# Main.net
KiCad netlist of a schematic drawn in Altium Designer
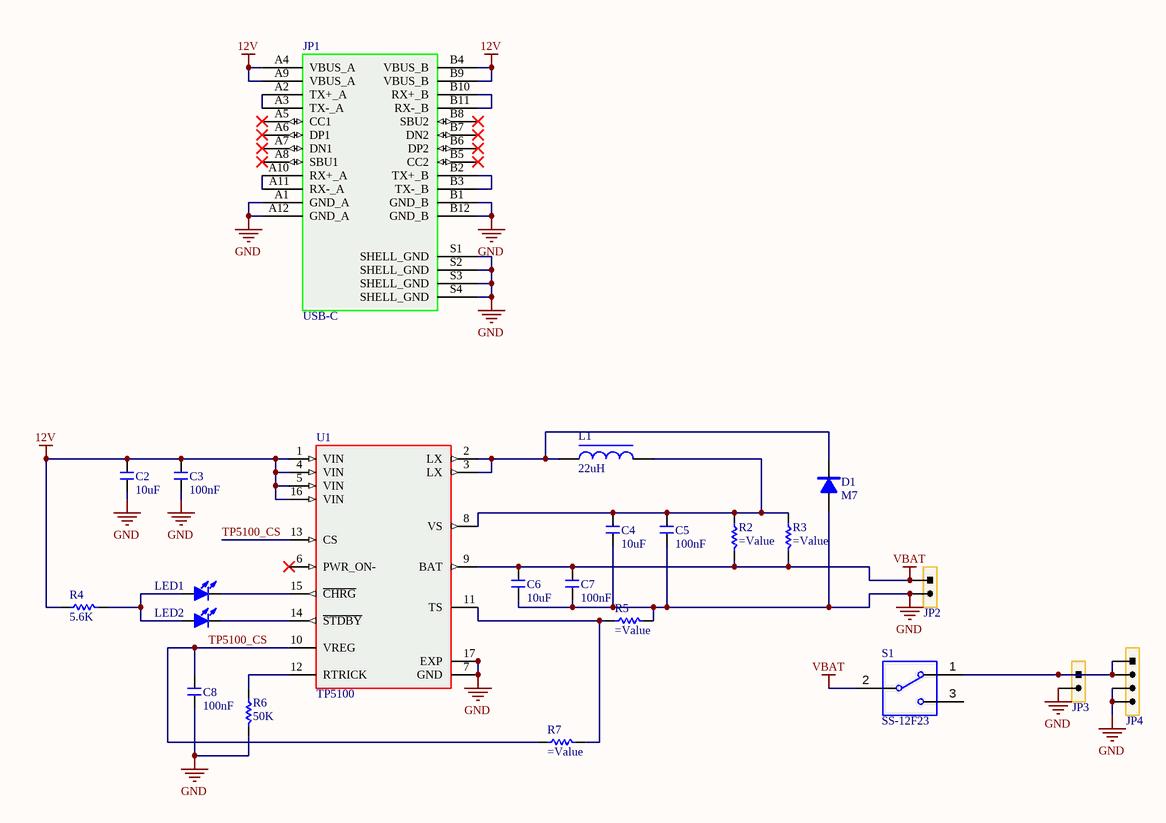
[diagram p0: Main.SchDoc]

(export (version "E")
  (design (tool "Eeschema 10.0.6"))
  (components
    (comp (ref "C2")
      (value "10uF")
      (footprint "C 0805")
      (description "Non-polar patch capacitor")
      (fields (field (name "版权归属") "源创客"))
      (libsource (lib "Passive (Resistor-Capacitor-Inductor-Veristor-Ferrite)") (part "C"))
    )
    (comp (ref "C3")
      (value "100nF")
      (footprint "C 0805")
      (description "Non-polar patch capacitor")
      (fields (field (name "版权归属") "源创客"))
      (libsource (lib "Passive (Resistor-Capacitor-Inductor-Veristor-Ferrite)") (part "C"))
    )
    (comp (ref "C4")
      (value "10uF")
      (footprint "C 0805")
      (description "Non-polar patch capacitor")
      (fields (field (name "版权归属") "源创客"))
      (libsource (lib "Passive (Resistor-Capacitor-Inductor-Veristor-Ferrite)") (part "C"))
    )
    (comp (ref "C5")
      (value "100nF")
      (footprint "C 0805")
      (description "Non-polar patch capacitor")
      (fields (field (name "版权归属") "源创客"))
      (libsource (lib "Passive (Resistor-Capacitor-Inductor-Veristor-Ferrite)") (part "C"))
    )
    (comp (ref "C6")
      (value "10uF")
      (footprint "C 0805")
      (description "Non-polar patch capacitor")
      (fields (field (name "版权归属") "源创客"))
      (libsource (lib "Passive (Resistor-Capacitor-Inductor-Veristor-Ferrite)") (part "C"))
    )
    (comp (ref "C7")
      (value "100nF")
      (footprint "C 0805")
      (description "Non-polar patch capacitor")
      (fields (field (name "版权归属") "源创客"))
      (libsource (lib "Passive (Resistor-Capacitor-Inductor-Veristor-Ferrite)") (part "C"))
    )
    (comp (ref "C8")
      (value "100nF")
      (footprint "C 0805")
      (description "Non-polar patch capacitor")
      (fields (field (name "版权归属") "源创客"))
      (libsource (lib "Passive (Resistor-Capacitor-Inductor-Veristor-Ferrite)") (part "C"))
    )
    (comp (ref "D1")
      (value "M7")
      (footprint "SMA")
      (description "Rectifier diode")
      (fields (field (name "版权归属") "源创客"))
      (libsource (lib "Diode-Zener-Rectifier Bridge") (part "M7"))
    )
    (comp (ref "JP1")
      (value "USB-C")
      (footprint "USB-C-RIGHT")
      (libsource (lib "IO (Power-USB-Serial-VGA-RJ-Audio-Buzzer)") (part "USB-C-RIGHT"))
    )
    (comp (ref "JP2")
      (value "HDR-1X2")
      (footprint "XH2.54-2P_H")
      (description "2P Connector")
      (fields (field (name "版权归属") "源创客"))
      (libsource (lib "Connectors") (part "Header 2"))
    )
    (comp (ref "JP3")
      (value "HDR-1X2")
      (footprint "XH2.54-2P_H")
      (description "2P Connector")
      (fields (field (name "版权归属") "源创客"))
      (libsource (lib "Connectors") (part "Header 2"))
    )
    (comp (ref "JP4")
      (value "HDR-1X4")
      (footprint "HDR-1X4")
      (description "4P Connector")
      (fields (field (name "版权归属") "源创客"))
      (libsource (lib "Connectors") (part "Header 4"))
    )
    (comp (ref "L1")
      (value "22uH")
      (footprint "CD54")
      (description "Chip power inductor")
      (fields (field (name "版权归属") "源创客"))
      (libsource (lib "Passive (Resistor-Capacitor-Inductor-Veristor-Ferrite)") (part "L-CD"))
    )
    (comp (ref "LED1")
      (value "LED-SMD")
      (footprint "LED 0603R")
      (description "Patch LED")
      (fields (field (name "版权归属") "源创客"))
      (libsource (lib "LED") (part "LED-SMD"))
    )
    (comp (ref "LED2")
      (value "LED-SMD")
      (footprint "LED 0603B")
      (description "Patch LED")
      (fields (field (name "版权归属") "源创客"))
      (libsource (lib "LED") (part "LED-SMD"))
    )
    (comp (ref "R2")
      (value "~")
      (footprint "R 1206")
      (description "Chip resistor")
      (fields (field (name "版权归属") "源创客"))
      (libsource (lib "Passive (Resistor-Capacitor-Inductor-Veristor-Ferrite)") (part "R"))
    )
    (comp (ref "R3")
      (value "~")
      (footprint "R 1206")
      (description "Chip resistor")
      (fields (field (name "版权归属") "源创客"))
      (libsource (lib "Passive (Resistor-Capacitor-Inductor-Veristor-Ferrite)") (part "R"))
    )
    (comp (ref "R4")
      (value "5.6K")
      (footprint "R 0805")
      (description "Chip resistor")
      (fields (field (name "版权归属") "源创客"))
      (libsource (lib "Passive (Resistor-Capacitor-Inductor-Veristor-Ferrite)") (part "R"))
    )
    (comp (ref "R5")
      (value "~")
      (footprint "R 0805")
      (description "Chip resistor")
      (fields (field (name "版权归属") "源创客"))
      (libsource (lib "Passive (Resistor-Capacitor-Inductor-Veristor-Ferrite)") (part "R"))
    )
    (comp (ref "R6")
      (value "50K")
      (footprint "R 0805")
      (description "Chip resistor")
      (fields (field (name "版权归属") "源创客"))
      (libsource (lib "Passive (Resistor-Capacitor-Inductor-Veristor-Ferrite)") (part "R"))
    )
    (comp (ref "R7")
      (value "~")
      (footprint "R 0805")
      (description "Chip resistor")
      (fields (field (name "版权归属") "源创客"))
      (libsource (lib "Passive (Resistor-Capacitor-Inductor-Veristor-Ferrite)") (part "R"))
    )
    (comp (ref "S1")
      (value "SS-12F23")
      (footprint "SS-12F23")
      (description "1-Way Sliding Switch")
      (fields (field (name "版权归属") "源创客"))
      (libsource (lib "Button") (part "SSW-1P"))
    )
    (comp (ref "U1")
      (value "TP5100")
      (footprint "QFN16_4*4")
      (description "Battery Charger")
      (libsource (lib "Integrated Circuit") (part "TP5100"))
    )
  )
  (nets
    (net (code "1") (name "/TP5100_CS") (class "Default")
      (node (ref "C8") (pin "2") (pinfunction "2_2") (pintype "passive"))
      (node (ref "R7") (pin "1") (pinfunction "1_1") (pintype "passive"))
      (node (ref "U1") (pin "10") (pinfunction "VREG_10") (pintype "passive"))
      (node (ref "U1") (pin "13") (pinfunction "CS_13") (pintype "input"))
    )
    (net (code "2") (name "12V") (class "Default")
      (node (ref "C2") (pin "2") (pinfunction "2_2") (pintype "passive"))
      (node (ref "C3") (pin "2") (pinfunction "2_2") (pintype "passive"))
      (node (ref "JP1") (pin "A4") (pinfunction "VBUS_A_A4") (pintype "power_in"))
      (node (ref "JP1") (pin "A9") (pinfunction "VBUS_A_A9") (pintype "power_in"))
      (node (ref "JP1") (pin "B4") (pinfunction "VBUS_B_B4") (pintype "power_in"))
      (node (ref "JP1") (pin "B9") (pinfunction "VBUS_B_B9") (pintype "power_in"))
      (node (ref "R4") (pin "1") (pinfunction "1_1") (pintype "passive"))
      (node (ref "U1") (pin "1") (pinfunction "VIN_1") (pintype "input"))
      (node (ref "U1") (pin "16") (pinfunction "VIN_16") (pintype "input"))
      (node (ref "U1") (pin "4") (pinfunction "VIN_4") (pintype "input"))
      (node (ref "U1") (pin "5") (pinfunction "VIN_5") (pintype "input"))
    )
    (net (code "3") (name "GND") (class "Default")
      (node (ref "C2") (pin "1") (pinfunction "1_1") (pintype "passive"))
      (node (ref "C3") (pin "1") (pinfunction "1_1") (pintype "passive"))
      (node (ref "C4") (pin "1") (pinfunction "1_1") (pintype "passive"))
      (node (ref "C5") (pin "1") (pinfunction "1_1") (pintype "passive"))
      (node (ref "C6") (pin "1") (pinfunction "1_1") (pintype "passive"))
      (node (ref "C7") (pin "1") (pinfunction "1_1") (pintype "passive"))
      (node (ref "C8") (pin "1") (pinfunction "1_1") (pintype "passive"))
      (node (ref "D1") (pin "1") (pinfunction "A_1") (pintype "passive"))
      (node (ref "JP1") (pin "A1") (pinfunction "GND_A_A1") (pintype "power_in"))
      (node (ref "JP1") (pin "A12") (pinfunction "GND_A_A12") (pintype "power_in"))
      (node (ref "JP1") (pin "B1") (pinfunction "GND_B_B1") (pintype "power_in"))
      (node (ref "JP1") (pin "B12") (pinfunction "GND_B_B12") (pintype "power_in"))
      (node (ref "JP1") (pin "S1") (pinfunction "SHELL_GND_S1") (pintype "power_in"))
      (node (ref "JP1") (pin "S2") (pinfunction "SHELL_GND_S2") (pintype "power_in"))
      (node (ref "JP1") (pin "S3") (pinfunction "SHELL_GND_S3") (pintype "power_in"))
      (node (ref "JP1") (pin "S4") (pinfunction "SHELL_GND_S4") (pintype "power_in"))
      (node (ref "JP2") (pin "2") (pintype "passive"))
      (node (ref "JP3") (pin "2") (pintype "passive"))
      (node (ref "JP4") (pin "3") (pintype "passive"))
      (node (ref "JP4") (pin "4") (pintype "passive"))
      (node (ref "R5") (pin "2") (pinfunction "2_2") (pintype "passive"))
      (node (ref "R6") (pin "2") (pinfunction "2_2") (pintype "passive"))
      (node (ref "U1") (pin "17") (pinfunction "EXP_17") (pintype "passive"))
      (node (ref "U1") (pin "7") (pinfunction "GND_7") (pintype "power_in"))
    )
    (net (code "4") (name "Net-(D1-K)") (class "Default")
      (node (ref "D1") (pin "2") (pinfunction "K_2") (pintype "passive"))
      (node (ref "L1") (pin "1") (pinfunction "1_1") (pintype "passive"))
      (node (ref "U1") (pin "2") (pinfunction "LX_2") (pintype "output"))
      (node (ref "U1") (pin "3") (pinfunction "LX_3") (pintype "output"))
    )
    (net (code "5") (name "Net-(JP1-RX+_A)") (class "Default")
      (node (ref "JP1") (pin "A10") (pinfunction "RX+_A_A10") (pintype "power_in"))
      (node (ref "JP1") (pin "A11") (pinfunction "RX-_A_A11") (pintype "power_in"))
    )
    (net (code "6") (name "Net-(JP1-RX+_B)") (class "Default")
      (node (ref "JP1") (pin "B10") (pinfunction "RX+_B_B10") (pintype "power_in"))
      (node (ref "JP1") (pin "B11") (pinfunction "RX-_B_B11") (pintype "power_in"))
    )
    (net (code "7") (name "Net-(JP1-TX+_A)") (class "Default")
      (node (ref "JP1") (pin "A2") (pinfunction "TX+_A_A2") (pintype "power_in"))
      (node (ref "JP1") (pin "A3") (pinfunction "TX-_A_A3") (pintype "power_in"))
    )
    (net (code "8") (name "Net-(JP1-TX+_B)") (class "Default")
      (node (ref "JP1") (pin "B2") (pinfunction "TX+_B_B2") (pintype "power_in"))
      (node (ref "JP1") (pin "B3") (pinfunction "TX-_B_B3") (pintype "power_in"))
    )
    (net (code "9") (name "Net-(JP3-Pad1)") (class "Default")
      (node (ref "JP3") (pin "1") (pintype "passive"))
      (node (ref "JP4") (pin "1") (pintype "passive"))
      (node (ref "JP4") (pin "2") (pintype "passive"))
      (node (ref "S1") (pin "1") (pinfunction "1_1") (pintype "passive"))
    )
    (net (code "10") (name "Net-(LED1-A)") (class "Default")
      (node (ref "LED1") (pin "1") (pinfunction "A_1") (pintype "passive"))
      (node (ref "LED2") (pin "1") (pinfunction "A_1") (pintype "passive"))
      (node (ref "R4") (pin "2") (pinfunction "2_2") (pintype "passive"))
    )
    (net (code "11") (name "Net-(LED1-K)") (class "Default")
      (node (ref "LED1") (pin "2") (pinfunction "K_2") (pintype "passive"))
      (node (ref "U1") (pin "15") (pinfunction "~{CHRG}_15") (pintype "output"))
    )
    (net (code "12") (name "Net-(LED2-K)") (class "Default")
      (node (ref "LED2") (pin "2") (pinfunction "K_2") (pintype "passive"))
      (node (ref "U1") (pin "14") (pinfunction "~{STDBY}_14") (pintype "output"))
    )
    (net (code "13") (name "Net-(U1-RTRICK)") (class "Default")
      (node (ref "R6") (pin "1") (pinfunction "1_1") (pintype "passive"))
      (node (ref "U1") (pin "12") (pinfunction "RTRICK_12") (pintype "passive"))
    )
    (net (code "14") (name "Net-(U1-TS)") (class "Default")
      (node (ref "R5") (pin "1") (pinfunction "1_1") (pintype "passive"))
      (node (ref "R7") (pin "2") (pinfunction "2_2") (pintype "passive"))
      (node (ref "U1") (pin "11") (pinfunction "TS_11") (pintype "passive"))
    )
    (net (code "15") (name "Net-(U1-VS)") (class "Default")
      (node (ref "C4") (pin "2") (pinfunction "2_2") (pintype "passive"))
      (node (ref "C5") (pin "2") (pinfunction "2_2") (pintype "passive"))
      (node (ref "L1") (pin "2") (pinfunction "2_2") (pintype "passive"))
      (node (ref "R2") (pin "1") (pinfunction "1_1") (pintype "passive"))
      (node (ref "R3") (pin "1") (pinfunction "1_1") (pintype "passive"))
      (node (ref "U1") (pin "8") (pinfunction "VS_8") (pintype "output"))
    )
    (net (code "16") (name "VBAT") (class "Default")
      (node (ref "C6") (pin "2") (pinfunction "2_2") (pintype "passive"))
      (node (ref "C7") (pin "2") (pinfunction "2_2") (pintype "passive"))
      (node (ref "JP2") (pin "1") (pintype "passive"))
      (node (ref "R2") (pin "2") (pinfunction "2_2") (pintype "passive"))
      (node (ref "R3") (pin "2") (pinfunction "2_2") (pintype "passive"))
      (node (ref "S1") (pin "2") (pinfunction "2_2") (pintype "passive"))
      (node (ref "U1") (pin "9") (pinfunction "BAT_9") (pintype "output"))
    )
    (net (code "17") (name "unconnected-(JP1-CC1-PadA5)") (class "Default")
      (node (ref "JP1") (pin "A5") (pinfunction "CC1_A5") (pintype "bidirectional+no_connect"))
    )
    (net (code "18") (name "unconnected-(JP1-CC2-PadB5)") (class "Default")
      (node (ref "JP1") (pin "B5") (pinfunction "CC2_B5") (pintype "bidirectional+no_connect"))
    )
    (net (code "19") (name "unconnected-(JP1-DN1-PadA7)") (class "Default")
      (node (ref "JP1") (pin "A7") (pinfunction "DN1_A7") (pintype "bidirectional+no_connect"))
    )
    (net (code "20") (name "unconnected-(JP1-DN2-PadB7)") (class "Default")
      (node (ref "JP1") (pin "B7") (pinfunction "DN2_B7") (pintype "bidirectional+no_connect"))
    )
    (net (code "21") (name "unconnected-(JP1-DP1-PadA6)") (class "Default")
      (node (ref "JP1") (pin "A6") (pinfunction "DP1_A6") (pintype "bidirectional+no_connect"))
    )
    (net (code "22") (name "unconnected-(JP1-DP2-PadB6)") (class "Default")
      (node (ref "JP1") (pin "B6") (pinfunction "DP2_B6") (pintype "bidirectional+no_connect"))
    )
    (net (code "23") (name "unconnected-(JP1-SBU1-PadA8)") (class "Default")
      (node (ref "JP1") (pin "A8") (pinfunction "SBU1_A8") (pintype "bidirectional+no_connect"))
    )
    (net (code "24") (name "unconnected-(JP1-SBU2-PadB8)") (class "Default")
      (node (ref "JP1") (pin "B8") (pinfunction "SBU2_B8") (pintype "bidirectional+no_connect"))
    )
    (net (code "25") (name "unconnected-(S1-Pad3)") (class "Default")
      (node (ref "S1") (pin "3") (pinfunction "3_3") (pintype "passive"))
    )
    (net (code "26") (name "unconnected-(U1-PWR_ON--Pad6)") (class "Default")
      (node (ref "U1") (pin "6") (pinfunction "PWR_ON-_6") (pintype "input+no_connect"))
    )
  )
)
